# Skull_Candy_Lamp.net
KiCad netlist of a schematic drawn in EAGLE
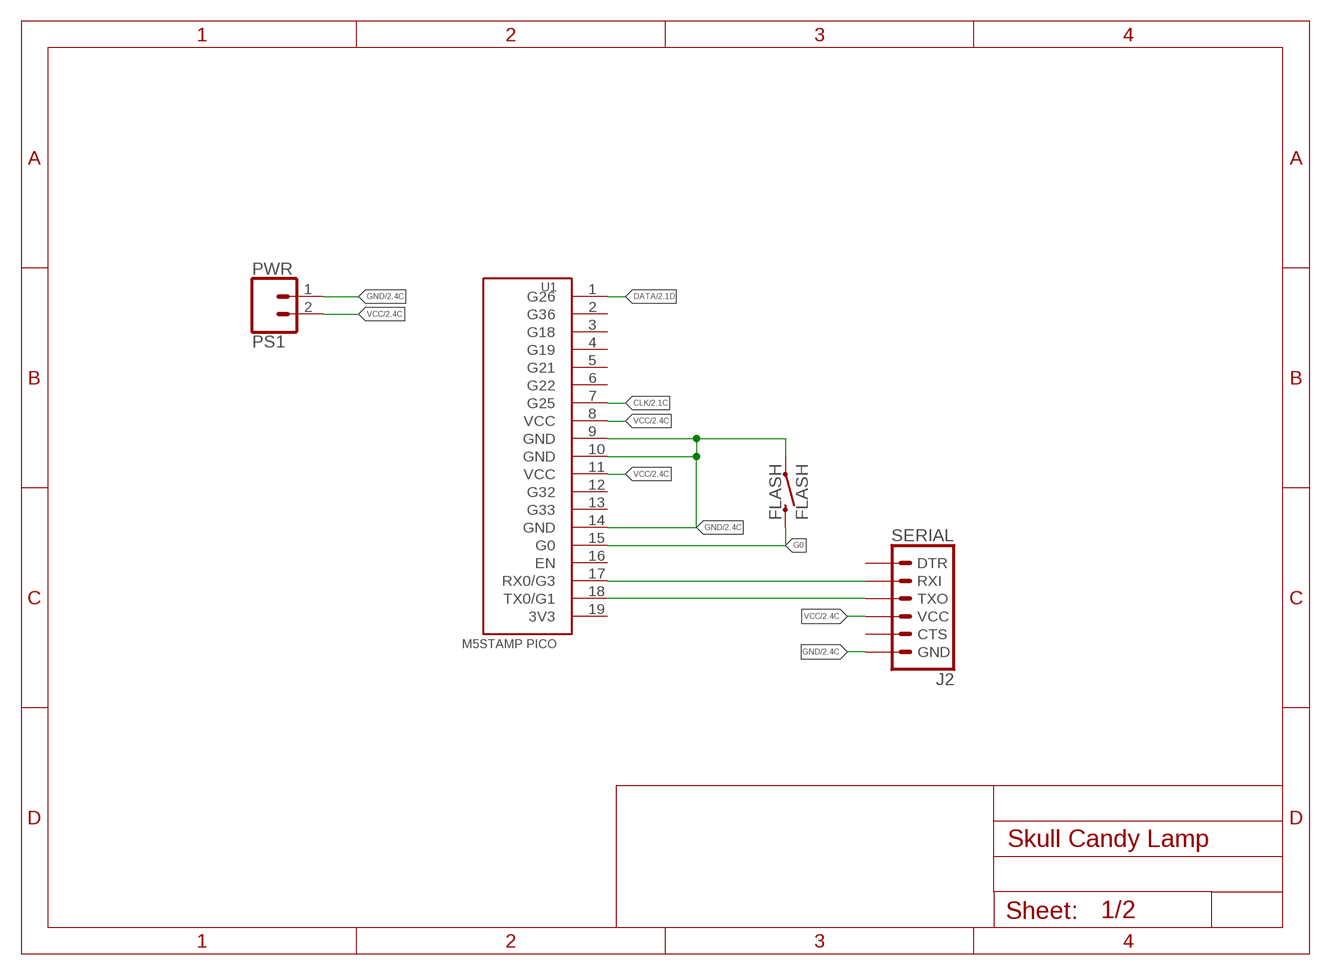
[diagram p0: schematic, sheet 1]
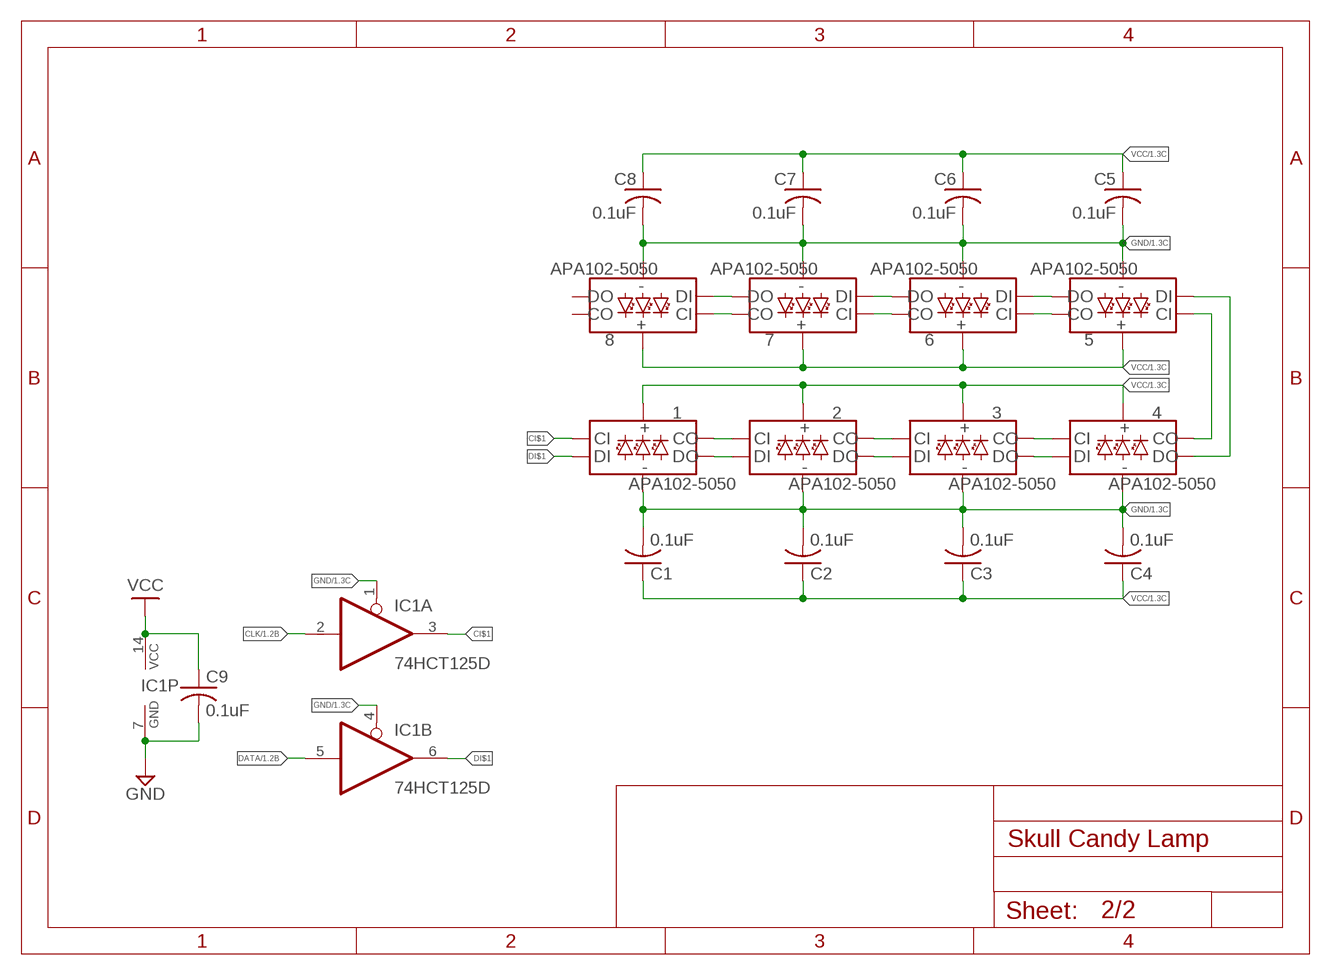
[diagram p1: schematic, sheet 2]

(export (version "E")
  (design (tool "Eeschema 10.0.6"))
  (components
    (comp (ref "FLASH")
      (value "FLASH")
      (footprint "eagle-import:TACTILE_SWITCH_SMD_5.2MM")
      (libsource (lib "eagle-import") (part "MOMENTARY-SWITCH-SPST-SMD-5.2MM"))
    )
    (comp (ref "J2")
      (value "SERIAL")
      (footprint "eagle-import:6_PIN_SERIAL_TARGET_SIDE_W_SILK")
      (libsource (lib "eagle-import") (part "6_PIN_SERIAL_TARGETSILK"))
    )
    (comp (ref "PS1")
      (value "PWR")
      (footprint "eagle-import:MOLEX-1X2_LOCK")
      (libsource (lib "eagle-import") (part "CONN_02POLAR_LOCK"))
    )
    (comp (ref "U1")
      (value "M5STAMP PICO")
      (footprint "eagle-import:M5STAMP-PICO")
      (libsource (lib "eagle-import") (part "M5STAMP-PICO"))
    )
    (comp (ref "1")
      (value "APA102-5050")
      (footprint "eagle-import:APA102-5050")
      (libsource (lib "eagle-import") (part "APA102-5050"))
    )
    (comp (ref "2")
      (value "APA102-5050")
      (footprint "eagle-import:APA102-5050")
      (libsource (lib "eagle-import") (part "APA102-5050"))
    )
    (comp (ref "3")
      (value "APA102-5050")
      (footprint "eagle-import:APA102-5050")
      (libsource (lib "eagle-import") (part "APA102-5050"))
    )
    (comp (ref "4")
      (value "APA102-5050")
      (footprint "eagle-import:APA102-5050")
      (libsource (lib "eagle-import") (part "APA102-5050"))
    )
    (comp (ref "5")
      (value "APA102-5050")
      (footprint "eagle-import:APA102-5050")
      (libsource (lib "eagle-import") (part "APA102-5050"))
    )
    (comp (ref "6")
      (value "APA102-5050")
      (footprint "eagle-import:APA102-5050")
      (libsource (lib "eagle-import") (part "APA102-5050"))
    )
    (comp (ref "7")
      (value "APA102-5050")
      (footprint "eagle-import:APA102-5050")
      (libsource (lib "eagle-import") (part "APA102-5050"))
    )
    (comp (ref "8")
      (value "APA102-5050")
      (footprint "eagle-import:APA102-5050")
      (libsource (lib "eagle-import") (part "APA102-5050"))
    )
    (comp (ref "C1")
      (value "0.1uF")
      (footprint "eagle-import:CAPC2012X110")
      (libsource (lib "eagle-import") (part "C-USCHIP-0805(2012-METRIC)_"))
    )
    (comp (ref "C2")
      (value "0.1uF")
      (footprint "eagle-import:CAPC2012X110")
      (libsource (lib "eagle-import") (part "C-USCHIP-0805(2012-METRIC)_"))
    )
    (comp (ref "C3")
      (value "0.1uF")
      (footprint "eagle-import:CAPC2012X110")
      (libsource (lib "eagle-import") (part "C-USCHIP-0805(2012-METRIC)_"))
    )
    (comp (ref "C4")
      (value "0.1uF")
      (footprint "eagle-import:CAPC2012X110")
      (libsource (lib "eagle-import") (part "C-USCHIP-0805(2012-METRIC)_"))
    )
    (comp (ref "C5")
      (value "0.1uF")
      (footprint "eagle-import:CAPC2012X110")
      (libsource (lib "eagle-import") (part "C-USCHIP-0805(2012-METRIC)_"))
    )
    (comp (ref "C6")
      (value "0.1uF")
      (footprint "eagle-import:CAPC2012X110")
      (libsource (lib "eagle-import") (part "C-USCHIP-0805(2012-METRIC)_"))
    )
    (comp (ref "C7")
      (value "0.1uF")
      (footprint "eagle-import:CAPC2012X110")
      (libsource (lib "eagle-import") (part "C-USCHIP-0805(2012-METRIC)_"))
    )
    (comp (ref "C8")
      (value "0.1uF")
      (footprint "eagle-import:CAPC2012X110")
      (libsource (lib "eagle-import") (part "C-USCHIP-0805(2012-METRIC)_"))
    )
    (comp (ref "C9")
      (value "0.1uF")
      (footprint "eagle-import:CAPC2012X110")
      (libsource (lib "eagle-import") (part "C-USCHIP-0805(2012-METRIC)_"))
    )
    (comp (ref "IC1")
      (value "74HCT125D")
      (footprint "eagle-import:SO14")
      (libsource (lib "eagle-import") (part "74125DHCT"))
    )
  )
  (nets
    (net (code "1") (name "3V3") (class "Default")
      (node (ref "U1") (pin "19") (pinfunction "3V3_19") (pintype "power_in"))
    )
    (net (code "2") (name "CI$1") (class "Default")
      (node (ref "1") (pin "P2") (pinfunction "CI_P2") (pintype "bidirectional"))
      (node (ref "IC1") (pin "3") (pinfunction "O_3") (pintype "tri_state"))
    )
    (net (code "3") (name "CLK") (class "Default")
      (node (ref "IC1") (pin "2") (pinfunction "I_2") (pintype "input"))
      (node (ref "U1") (pin "7") (pinfunction "G25_7") (pintype "bidirectional"))
    )
    (net (code "4") (name "DATA") (class "Default")
      (node (ref "IC1") (pin "5") (pinfunction "I_5") (pintype "input"))
      (node (ref "U1") (pin "1") (pinfunction "G26_1") (pintype "bidirectional"))
    )
    (net (code "5") (name "DI$1") (class "Default")
      (node (ref "1") (pin "P1") (pinfunction "DI_P1") (pintype "bidirectional"))
      (node (ref "IC1") (pin "6") (pinfunction "O_6") (pintype "tri_state"))
    )
    (net (code "6") (name "G0") (class "Default")
      (node (ref "FLASH") (pin "3") (pinfunction "2_3") (pintype "passive"))
      (node (ref "U1") (pin "15") (pinfunction "G0_15") (pintype "bidirectional"))
    )
    (net (code "7") (name "GND") (class "Default")
      (node (ref "1") (pin "P3") (pinfunction "GND_P3") (pintype "bidirectional"))
      (node (ref "2") (pin "P3") (pinfunction "GND_P3") (pintype "bidirectional"))
      (node (ref "3") (pin "P3") (pinfunction "GND_P3") (pintype "bidirectional"))
      (node (ref "4") (pin "P3") (pinfunction "GND_P3") (pintype "bidirectional"))
      (node (ref "5") (pin "P3") (pinfunction "GND_P3") (pintype "bidirectional"))
      (node (ref "6") (pin "P3") (pinfunction "GND_P3") (pintype "bidirectional"))
      (node (ref "7") (pin "P3") (pinfunction "GND_P3") (pintype "bidirectional"))
      (node (ref "8") (pin "P3") (pinfunction "GND_P3") (pintype "bidirectional"))
      (node (ref "C1") (pin "2") (pinfunction "2_2") (pintype "passive"))
      (node (ref "C2") (pin "2") (pinfunction "2_2") (pintype "passive"))
      (node (ref "C3") (pin "2") (pinfunction "2_2") (pintype "passive"))
      (node (ref "C4") (pin "2") (pinfunction "2_2") (pintype "passive"))
      (node (ref "C5") (pin "2") (pinfunction "2_2") (pintype "passive"))
      (node (ref "C6") (pin "2") (pinfunction "2_2") (pintype "passive"))
      (node (ref "C7") (pin "2") (pinfunction "2_2") (pintype "passive"))
      (node (ref "C8") (pin "2") (pinfunction "2_2") (pintype "passive"))
      (node (ref "C9") (pin "2") (pinfunction "2_2") (pintype "passive"))
      (node (ref "FLASH") (pin "1") (pinfunction "1_1") (pintype "passive"))
      (node (ref "IC1") (pin "1") (pinfunction "OE_1") (pintype "input"))
      (node (ref "IC1") (pin "4") (pinfunction "OE_4") (pintype "input"))
      (node (ref "IC1") (pin "7") (pinfunction "GND_7") (pintype "power_in"))
      (node (ref "J2") (pin "P$6") (pinfunction "GND_P$6") (pintype "passive"))
      (node (ref "PS1") (pin "1") (pinfunction "1_1") (pintype "passive"))
      (node (ref "U1") (pin "10") (pinfunction "GND_10") (pintype "power_in"))
      (node (ref "U1") (pin "14") (pinfunction "GND_14") (pintype "power_in"))
      (node (ref "U1") (pin "9") (pinfunction "GND_9") (pintype "power_in"))
    )
    (net (code "8") (name "Net-(1-CO)") (class "Default")
      (node (ref "1") (pin "P5") (pinfunction "CO_P5") (pintype "bidirectional"))
      (node (ref "2") (pin "P2") (pinfunction "CI_P2") (pintype "bidirectional"))
    )
    (net (code "9") (name "Net-(1-DO)") (class "Default")
      (node (ref "1") (pin "P6") (pinfunction "DO_P6") (pintype "bidirectional"))
      (node (ref "2") (pin "P1") (pinfunction "DI_P1") (pintype "bidirectional"))
    )
    (net (code "10") (name "Net-(2-CO)") (class "Default")
      (node (ref "2") (pin "P5") (pinfunction "CO_P5") (pintype "bidirectional"))
      (node (ref "3") (pin "P2") (pinfunction "CI_P2") (pintype "bidirectional"))
    )
    (net (code "11") (name "Net-(2-DO)") (class "Default")
      (node (ref "2") (pin "P6") (pinfunction "DO_P6") (pintype "bidirectional"))
      (node (ref "3") (pin "P1") (pinfunction "DI_P1") (pintype "bidirectional"))
    )
    (net (code "12") (name "Net-(3-CO)") (class "Default")
      (node (ref "3") (pin "P5") (pinfunction "CO_P5") (pintype "bidirectional"))
      (node (ref "4") (pin "P2") (pinfunction "CI_P2") (pintype "bidirectional"))
    )
    (net (code "13") (name "Net-(3-DO)") (class "Default")
      (node (ref "3") (pin "P6") (pinfunction "DO_P6") (pintype "bidirectional"))
      (node (ref "4") (pin "P1") (pinfunction "DI_P1") (pintype "bidirectional"))
    )
    (net (code "14") (name "Net-(4-CO)") (class "Default")
      (node (ref "4") (pin "P5") (pinfunction "CO_P5") (pintype "bidirectional"))
      (node (ref "5") (pin "P2") (pinfunction "CI_P2") (pintype "bidirectional"))
    )
    (net (code "15") (name "Net-(4-DO)") (class "Default")
      (node (ref "4") (pin "P6") (pinfunction "DO_P6") (pintype "bidirectional"))
      (node (ref "5") (pin "P1") (pinfunction "DI_P1") (pintype "bidirectional"))
    )
    (net (code "16") (name "Net-(5-CO)") (class "Default")
      (node (ref "5") (pin "P5") (pinfunction "CO_P5") (pintype "bidirectional"))
      (node (ref "6") (pin "P2") (pinfunction "CI_P2") (pintype "bidirectional"))
    )
    (net (code "17") (name "Net-(5-DO)") (class "Default")
      (node (ref "5") (pin "P6") (pinfunction "DO_P6") (pintype "bidirectional"))
      (node (ref "6") (pin "P1") (pinfunction "DI_P1") (pintype "bidirectional"))
    )
    (net (code "18") (name "Net-(6-CO)") (class "Default")
      (node (ref "6") (pin "P5") (pinfunction "CO_P5") (pintype "bidirectional"))
      (node (ref "7") (pin "P2") (pinfunction "CI_P2") (pintype "bidirectional"))
    )
    (net (code "19") (name "Net-(6-DO)") (class "Default")
      (node (ref "6") (pin "P6") (pinfunction "DO_P6") (pintype "bidirectional"))
      (node (ref "7") (pin "P1") (pinfunction "DI_P1") (pintype "bidirectional"))
    )
    (net (code "20") (name "Net-(7-CO)") (class "Default")
      (node (ref "7") (pin "P5") (pinfunction "CO_P5") (pintype "bidirectional"))
      (node (ref "8") (pin "P2") (pinfunction "CI_P2") (pintype "bidirectional"))
    )
    (net (code "21") (name "Net-(7-DO)") (class "Default")
      (node (ref "7") (pin "P6") (pinfunction "DO_P6") (pintype "bidirectional"))
      (node (ref "8") (pin "P1") (pinfunction "DI_P1") (pintype "bidirectional"))
    )
    (net (code "22") (name "Net-(J2-RXI)") (class "Default")
      (node (ref "J2") (pin "P$3") (pinfunction "RXI_P$3") (pintype "passive"))
      (node (ref "U1") (pin "17") (pinfunction "RX0/G3_17") (pintype "bidirectional"))
    )
    (net (code "23") (name "Net-(J2-TXO)") (class "Default")
      (node (ref "J2") (pin "P$2") (pinfunction "TXO_P$2") (pintype "passive"))
      (node (ref "U1") (pin "18") (pinfunction "TX0/G1_18") (pintype "bidirectional"))
    )
    (net (code "24") (name "VCC") (class "Default")
      (node (ref "1") (pin "P4") (pinfunction "VCC_P4") (pintype "bidirectional"))
      (node (ref "2") (pin "P4") (pinfunction "VCC_P4") (pintype "bidirectional"))
      (node (ref "3") (pin "P4") (pinfunction "VCC_P4") (pintype "bidirectional"))
      (node (ref "4") (pin "P4") (pinfunction "VCC_P4") (pintype "bidirectional"))
      (node (ref "5") (pin "P4") (pinfunction "VCC_P4") (pintype "bidirectional"))
      (node (ref "6") (pin "P4") (pinfunction "VCC_P4") (pintype "bidirectional"))
      (node (ref "7") (pin "P4") (pinfunction "VCC_P4") (pintype "bidirectional"))
      (node (ref "8") (pin "P4") (pinfunction "VCC_P4") (pintype "bidirectional"))
      (node (ref "C1") (pin "1") (pinfunction "1_1") (pintype "passive"))
      (node (ref "C2") (pin "1") (pinfunction "1_1") (pintype "passive"))
      (node (ref "C3") (pin "1") (pinfunction "1_1") (pintype "passive"))
      (node (ref "C4") (pin "1") (pinfunction "1_1") (pintype "passive"))
      (node (ref "C5") (pin "1") (pinfunction "1_1") (pintype "passive"))
      (node (ref "C6") (pin "1") (pinfunction "1_1") (pintype "passive"))
      (node (ref "C7") (pin "1") (pinfunction "1_1") (pintype "passive"))
      (node (ref "C8") (pin "1") (pinfunction "1_1") (pintype "passive"))
      (node (ref "C9") (pin "1") (pinfunction "1_1") (pintype "passive"))
      (node (ref "IC1") (pin "14") (pinfunction "VCC_14") (pintype "power_in"))
      (node (ref "J2") (pin "P$4") (pinfunction "VCC_P$4") (pintype "passive"))
      (node (ref "PS1") (pin "2") (pinfunction "2_2") (pintype "passive"))
      (node (ref "U1") (pin "11") (pinfunction "VCC_11") (pintype "power_in"))
      (node (ref "U1") (pin "8") (pinfunction "VCC_8") (pintype "power_in"))
    )
    (net (code "25") (name "unconnected-(8-CO-PadP5)") (class "Default")
      (node (ref "8") (pin "P5") (pinfunction "CO_P5") (pintype "bidirectional"))
    )
    (net (code "26") (name "unconnected-(8-DO-PadP6)") (class "Default")
      (node (ref "8") (pin "P6") (pinfunction "DO_P6") (pintype "bidirectional"))
    )
    (net (code "27") (name "unconnected-(J2-CTS-PadP$5)") (class "Default")
      (node (ref "J2") (pin "P$5") (pinfunction "CTS_P$5") (pintype "passive"))
    )
    (net (code "28") (name "unconnected-(J2-DTR-PadP$1)") (class "Default")
      (node (ref "J2") (pin "P$1") (pinfunction "DTR_P$1") (pintype "passive"))
    )
    (net (code "29") (name "unconnected-(U1-EN-Pad16)") (class "Default")
      (node (ref "U1") (pin "16") (pinfunction "EN_16") (pintype "passive"))
    )
    (net (code "30") (name "unconnected-(U1-G18-Pad3)") (class "Default")
      (node (ref "U1") (pin "3") (pinfunction "G18_3") (pintype "bidirectional"))
    )
    (net (code "31") (name "unconnected-(U1-G19-Pad4)") (class "Default")
      (node (ref "U1") (pin "4") (pinfunction "G19_4") (pintype "bidirectional"))
    )
    (net (code "32") (name "unconnected-(U1-G21-Pad5)") (class "Default")
      (node (ref "U1") (pin "5") (pinfunction "G21_5") (pintype "bidirectional"))
    )
    (net (code "33") (name "unconnected-(U1-G22-Pad6)") (class "Default")
      (node (ref "U1") (pin "6") (pinfunction "G22_6") (pintype "bidirectional"))
    )
    (net (code "34") (name "unconnected-(U1-G32-Pad12)") (class "Default")
      (node (ref "U1") (pin "12") (pinfunction "G32_12") (pintype "bidirectional"))
    )
    (net (code "35") (name "unconnected-(U1-G33-Pad13)") (class "Default")
      (node (ref "U1") (pin "13") (pinfunction "G33_13") (pintype "bidirectional"))
    )
    (net (code "36") (name "unconnected-(U1-G36-Pad2)") (class "Default")
      (node (ref "U1") (pin "2") (pinfunction "G36_2") (pintype "input"))
    )
  )
)
